# breath_led.net
KiCad netlist of a schematic drawn in Altium Designer
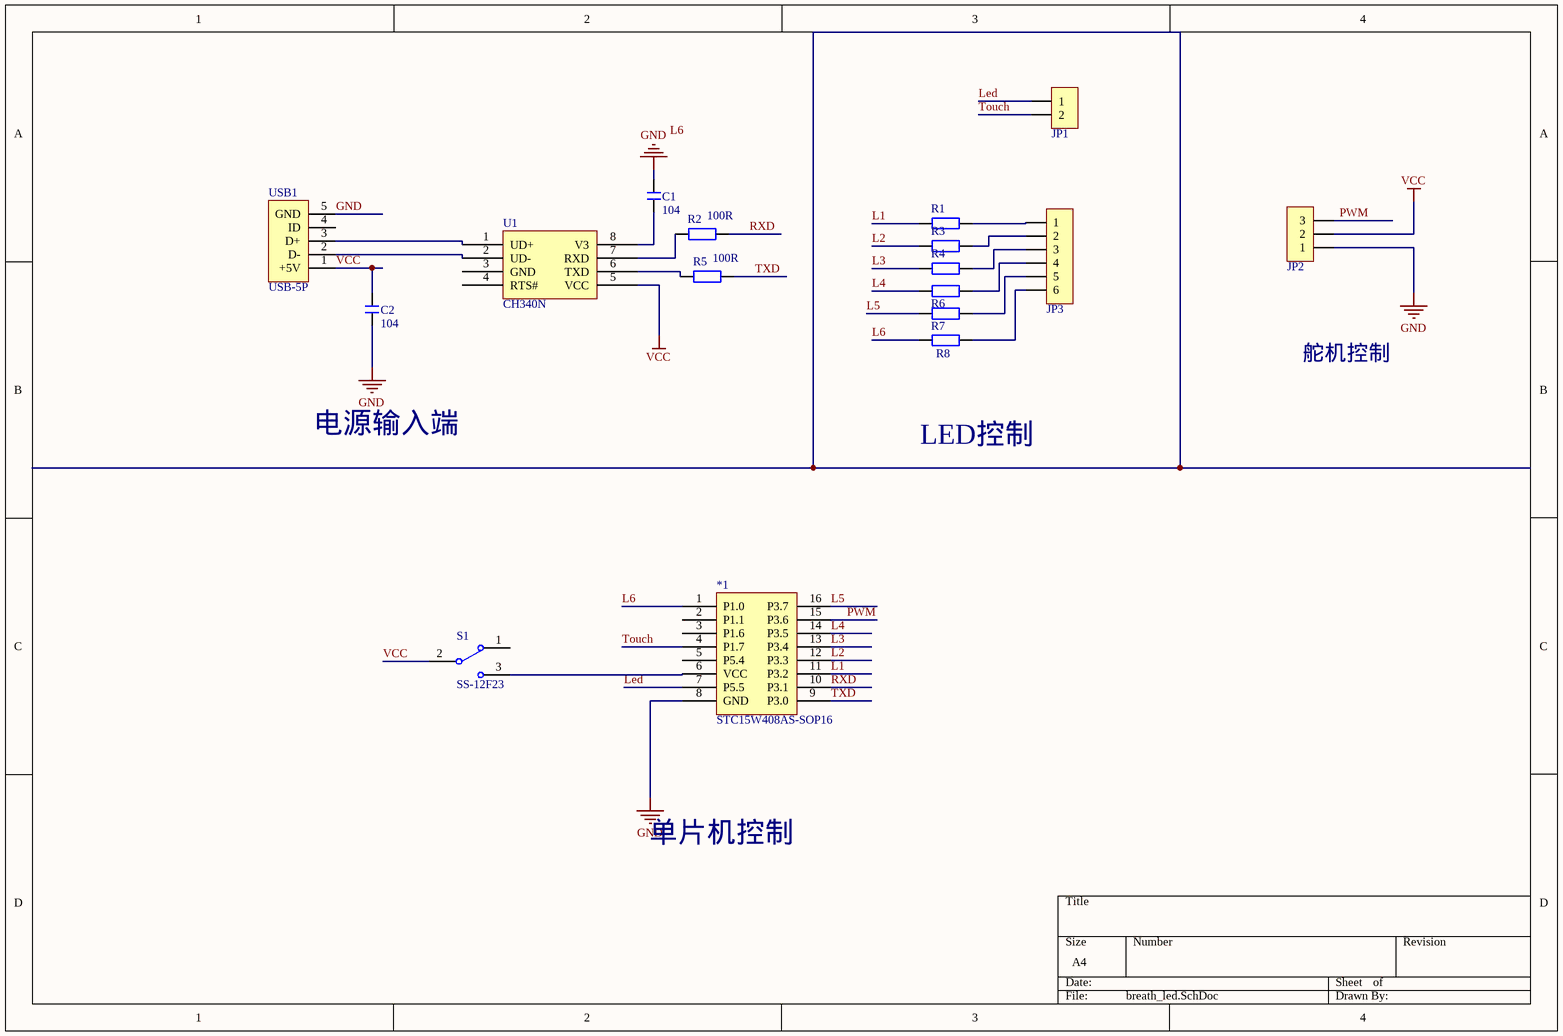
[diagram p0: breath_led.SchDoc]

(export (version "E")
  (design (tool "Eeschema 10.0.6"))
  (components
    (comp (ref "*1")
      (value "STC15W408AS-SOP16")
      (footprint "SOP16_M")
      (libsource (lib "XDB_原理图库") (part "STC8F2K16S2-SOP16"))
    )
    (comp (ref "C1")
      (value "104")
      (footprint "C 0805")
      (description "无极性贴片电容")
      (fields (field (name "版权归属") "黎明电子style"))
      (libsource (lib "电阻-电容-电感") (part "C"))
    )
    (comp (ref "C2")
      (value "104")
      (footprint "C 0805")
      (description "无极性贴片电容")
      (fields (field (name "版权归属") "黎明电子style"))
      (libsource (lib "电阻-电容-电感") (part "C"))
    )
    (comp (ref "JP1")
      (value "HDR-1X2")
      (footprint "HDR-1X2")
      (description "2P接插件")
      (fields (field (name "版权归属") "黎明电子style"))
      (libsource (lib "接插件") (part "Header 2"))
    )
    (comp (ref "JP2")
      (value "HDR-1X3")
      (footprint "HDR-1X3")
      (description "3P接插件")
      (fields (field (name "版权归属") "黎明电子style"))
      (libsource (lib "接插件") (part "Header 3"))
    )
    (comp (ref "JP3")
      (value "HDR-1X6")
      (footprint "HDR-1X6")
      (description "6P接插件")
      (fields (field (name "版权归属") "黎明电子style"))
      (libsource (lib "接插件") (part "Header 6"))
    )
    (comp (ref "R1")
      (value "1K")
      (footprint "R 0805")
      (description "贴片电阻")
      (fields (field (name "版权归属") "黎明电子style"))
      (libsource (lib "电阻-电容-电感") (part "R"))
    )
    (comp (ref "R2")
      (value "100R")
      (footprint "R 0805")
      (description "贴片电阻")
      (fields (field (name "版权归属") "黎明电子style"))
      (libsource (lib "电阻-电容-电感") (part "R"))
    )
    (comp (ref "R3")
      (value "1K")
      (footprint "R 0805")
      (description "贴片电阻")
      (fields (field (name "版权归属") "黎明电子style"))
      (libsource (lib "电阻-电容-电感") (part "R"))
    )
    (comp (ref "R4")
      (value "1K")
      (footprint "R 0805")
      (description "贴片电阻")
      (fields (field (name "版权归属") "黎明电子style"))
      (libsource (lib "电阻-电容-电感") (part "R"))
    )
    (comp (ref "R5")
      (value "100R")
      (footprint "R 0805")
      (description "贴片电阻")
      (fields (field (name "版权归属") "黎明电子style"))
      (libsource (lib "电阻-电容-电感") (part "R"))
    )
    (comp (ref "R6")
      (value "1K")
      (footprint "R 0805")
      (description "贴片电阻")
      (fields (field (name "版权归属") "黎明电子style"))
      (libsource (lib "电阻-电容-电感") (part "R"))
    )
    (comp (ref "R7")
      (value "1K")
      (footprint "R 0805")
      (description "贴片电阻")
      (fields (field (name "版权归属") "黎明电子style"))
      (libsource (lib "电阻-电容-电感") (part "R"))
    )
    (comp (ref "R8")
      (value "1K")
      (footprint "R 0805")
      (description "贴片电阻")
      (fields (field (name "版权归属") "黎明电子style"))
      (libsource (lib "电阻-电容-电感") (part "R"))
    )
    (comp (ref "S1")
      (value "SS-12F23")
      (footprint "MSK-12C01-07")
      (description "1路波动开关")
      (fields (field (name "版权归属") "黎明电子style"))
      (libsource (lib "按键-开关") (part "SSW-1P"))
    )
    (comp (ref "U1") (value "CH340N") (footprint "SOP8W_L") (libsource (lib "CH340T") (part "SOP20")))
    (comp (ref "USB1")
      (value "USB-5P")
      (footprint "USB-MICRO_A")
      (description "微型USB母座")
      (fields (field (name "版权归属") "黎明电子style"))
      (libsource (lib "接口类") (part "USB-5P"))
    )
  )
  (nets
    (net (code "1") (name "/L1") (class "Default")
      (node (ref "*1") (pin "11") (pinfunction "P3.2_11") (pintype "passive"))
      (node (ref "R1") (pin "1") (pinfunction "1_1") (pintype "passive"))
    )
    (net (code "2") (name "/L2") (class "Default")
      (node (ref "*1") (pin "12") (pinfunction "P3.3_12") (pintype "passive"))
      (node (ref "R3") (pin "1") (pinfunction "1_1") (pintype "passive"))
    )
    (net (code "3") (name "/L3") (class "Default")
      (node (ref "*1") (pin "13") (pinfunction "P3.4_13") (pintype "passive"))
      (node (ref "R4") (pin "1") (pinfunction "1_1") (pintype "passive"))
    )
    (net (code "4") (name "/L4") (class "Default")
      (node (ref "*1") (pin "14") (pinfunction "P3.5_14") (pintype "passive"))
      (node (ref "R6") (pin "1") (pinfunction "1_1") (pintype "passive"))
    )
    (net (code "5") (name "/L5") (class "Default")
      (node (ref "*1") (pin "16") (pinfunction "P3.7_16") (pintype "passive"))
      (node (ref "R7") (pin "1") (pinfunction "1_1") (pintype "passive"))
    )
    (net (code "6") (name "/L6") (class "Default")
      (node (ref "*1") (pin "1") (pinfunction "P1.0_1") (pintype "passive"))
      (node (ref "R8") (pin "1") (pinfunction "1_1") (pintype "passive"))
    )
    (net (code "7") (name "/Led") (class "Default")
      (node (ref "*1") (pin "7") (pinfunction "P5.5_7") (pintype "passive"))
      (node (ref "JP1") (pin "1") (pinfunction "1_1") (pintype "passive"))
    )
    (net (code "8") (name "/PWM") (class "Default")
      (node (ref "*1") (pin "15") (pinfunction "P3.6_15") (pintype "passive"))
      (node (ref "JP2") (pin "3") (pinfunction "3_3") (pintype "passive"))
    )
    (net (code "9") (name "/RXD") (class "Default")
      (node (ref "*1") (pin "10") (pinfunction "P3.1_10") (pintype "passive"))
      (node (ref "R2") (pin "2") (pinfunction "2_2") (pintype "passive"))
    )
    (net (code "10") (name "/TXD") (class "Default")
      (node (ref "*1") (pin "9") (pinfunction "P3.0_9") (pintype "passive"))
      (node (ref "R5") (pin "2") (pinfunction "2_2") (pintype "passive"))
    )
    (net (code "11") (name "/Touch") (class "Default")
      (node (ref "*1") (pin "4") (pinfunction "P1.7_4") (pintype "passive"))
      (node (ref "JP1") (pin "2") (pinfunction "2_2") (pintype "passive"))
    )
    (net (code "12") (name "GND") (class "Default")
      (node (ref "*1") (pin "8") (pinfunction "GND_8") (pintype "passive"))
      (node (ref "C1") (pin "2") (pinfunction "2_2") (pintype "passive"))
      (node (ref "C2") (pin "1") (pinfunction "1_1") (pintype "passive"))
      (node (ref "JP2") (pin "1") (pinfunction "1_1") (pintype "passive"))
      (node (ref "USB1") (pin "5") (pinfunction "GND_5") (pintype "passive"))
    )
    (net (code "13") (name "Net-(*1-VCC)") (class "Default")
      (node (ref "*1") (pin "6") (pinfunction "VCC_6") (pintype "passive"))
      (node (ref "S1") (pin "3") (pinfunction "3_3") (pintype "passive"))
    )
    (net (code "14") (name "Net-(JP3-Pad1)") (class "Default")
      (node (ref "JP3") (pin "1") (pinfunction "1_1") (pintype "passive"))
      (node (ref "R1") (pin "2") (pinfunction "2_2") (pintype "passive"))
    )
    (net (code "15") (name "Net-(JP3-Pad2)") (class "Default")
      (node (ref "JP3") (pin "2") (pinfunction "2_2") (pintype "passive"))
      (node (ref "R3") (pin "2") (pinfunction "2_2") (pintype "passive"))
    )
    (net (code "16") (name "Net-(JP3-Pad3)") (class "Default")
      (node (ref "JP3") (pin "3") (pinfunction "3_3") (pintype "passive"))
      (node (ref "R4") (pin "2") (pinfunction "2_2") (pintype "passive"))
    )
    (net (code "17") (name "Net-(JP3-Pad4)") (class "Default")
      (node (ref "JP3") (pin "4") (pinfunction "4_4") (pintype "passive"))
      (node (ref "R6") (pin "2") (pinfunction "2_2") (pintype "passive"))
    )
    (net (code "18") (name "Net-(JP3-Pad5)") (class "Default")
      (node (ref "JP3") (pin "5") (pinfunction "5_5") (pintype "passive"))
      (node (ref "R7") (pin "2") (pinfunction "2_2") (pintype "passive"))
    )
    (net (code "19") (name "Net-(JP3-Pad6)") (class "Default")
      (node (ref "JP3") (pin "6") (pinfunction "6_6") (pintype "passive"))
      (node (ref "R8") (pin "2") (pinfunction "2_2") (pintype "passive"))
    )
    (net (code "20") (name "Net-(U1-RXD)") (class "Default")
      (node (ref "R2") (pin "1") (pinfunction "1_1") (pintype "passive"))
      (node (ref "U1") (pin "7") (pinfunction "RXD_7") (pintype "passive"))
    )
    (net (code "21") (name "Net-(U1-TXD)") (class "Default")
      (node (ref "R5") (pin "1") (pinfunction "1_1") (pintype "passive"))
      (node (ref "U1") (pin "6") (pinfunction "TXD_6") (pintype "passive"))
    )
    (net (code "22") (name "Net-(U1-UD+)") (class "Default")
      (node (ref "U1") (pin "1") (pinfunction "UD+_1") (pintype "passive"))
      (node (ref "USB1") (pin "3") (pinfunction "D+_3") (pintype "passive"))
    )
    (net (code "23") (name "Net-(U1-UD-)") (class "Default")
      (node (ref "U1") (pin "2") (pinfunction "UD-_2") (pintype "passive"))
      (node (ref "USB1") (pin "2") (pinfunction "D-_2") (pintype "passive"))
    )
    (net (code "24") (name "Net-(U1-V3)") (class "Default")
      (node (ref "C1") (pin "1") (pinfunction "1_1") (pintype "passive"))
      (node (ref "U1") (pin "8") (pinfunction "V3_8") (pintype "passive"))
    )
    (net (code "25") (name "VCC") (class "Default")
      (node (ref "C2") (pin "2") (pinfunction "2_2") (pintype "passive"))
      (node (ref "JP2") (pin "2") (pinfunction "2_2") (pintype "passive"))
      (node (ref "S1") (pin "2") (pinfunction "2_2") (pintype "passive"))
      (node (ref "U1") (pin "5") (pinfunction "VCC_5") (pintype "passive"))
      (node (ref "USB1") (pin "1") (pinfunction "+5V_1") (pintype "passive"))
    )
    (net (code "26") (name "unconnected-(*1-P1.1-Pad2)") (class "Default")
      (node (ref "*1") (pin "2") (pinfunction "P1.1_2") (pintype "passive"))
    )
    (net (code "27") (name "unconnected-(*1-P1.6-Pad3)") (class "Default")
      (node (ref "*1") (pin "3") (pinfunction "P1.6_3") (pintype "passive"))
    )
    (net (code "28") (name "unconnected-(*1-P5.4-Pad5)") (class "Default")
      (node (ref "*1") (pin "5") (pinfunction "P5.4_5") (pintype "passive"))
    )
    (net (code "29") (name "unconnected-(S1-Pad1)") (class "Default")
      (node (ref "S1") (pin "1") (pinfunction "1_1") (pintype "passive"))
    )
    (net (code "30") (name "unconnected-(U1-GND-Pad3)") (class "Default")
      (node (ref "U1") (pin "3") (pinfunction "GND_3") (pintype "passive"))
    )
    (net (code "31") (name "unconnected-(U1-RTS#-Pad4)") (class "Default")
      (node (ref "U1") (pin "4") (pinfunction "RTS#_4") (pintype "passive"))
    )
    (net (code "32") (name "unconnected-(USB1-ID-Pad4)") (class "Default")
      (node (ref "USB1") (pin "4") (pinfunction "ID_4") (pintype "passive"))
    )
  )
)
